# MCPS_Power_030520.net
KiCad netlist of a schematic drawn in Altium Designer
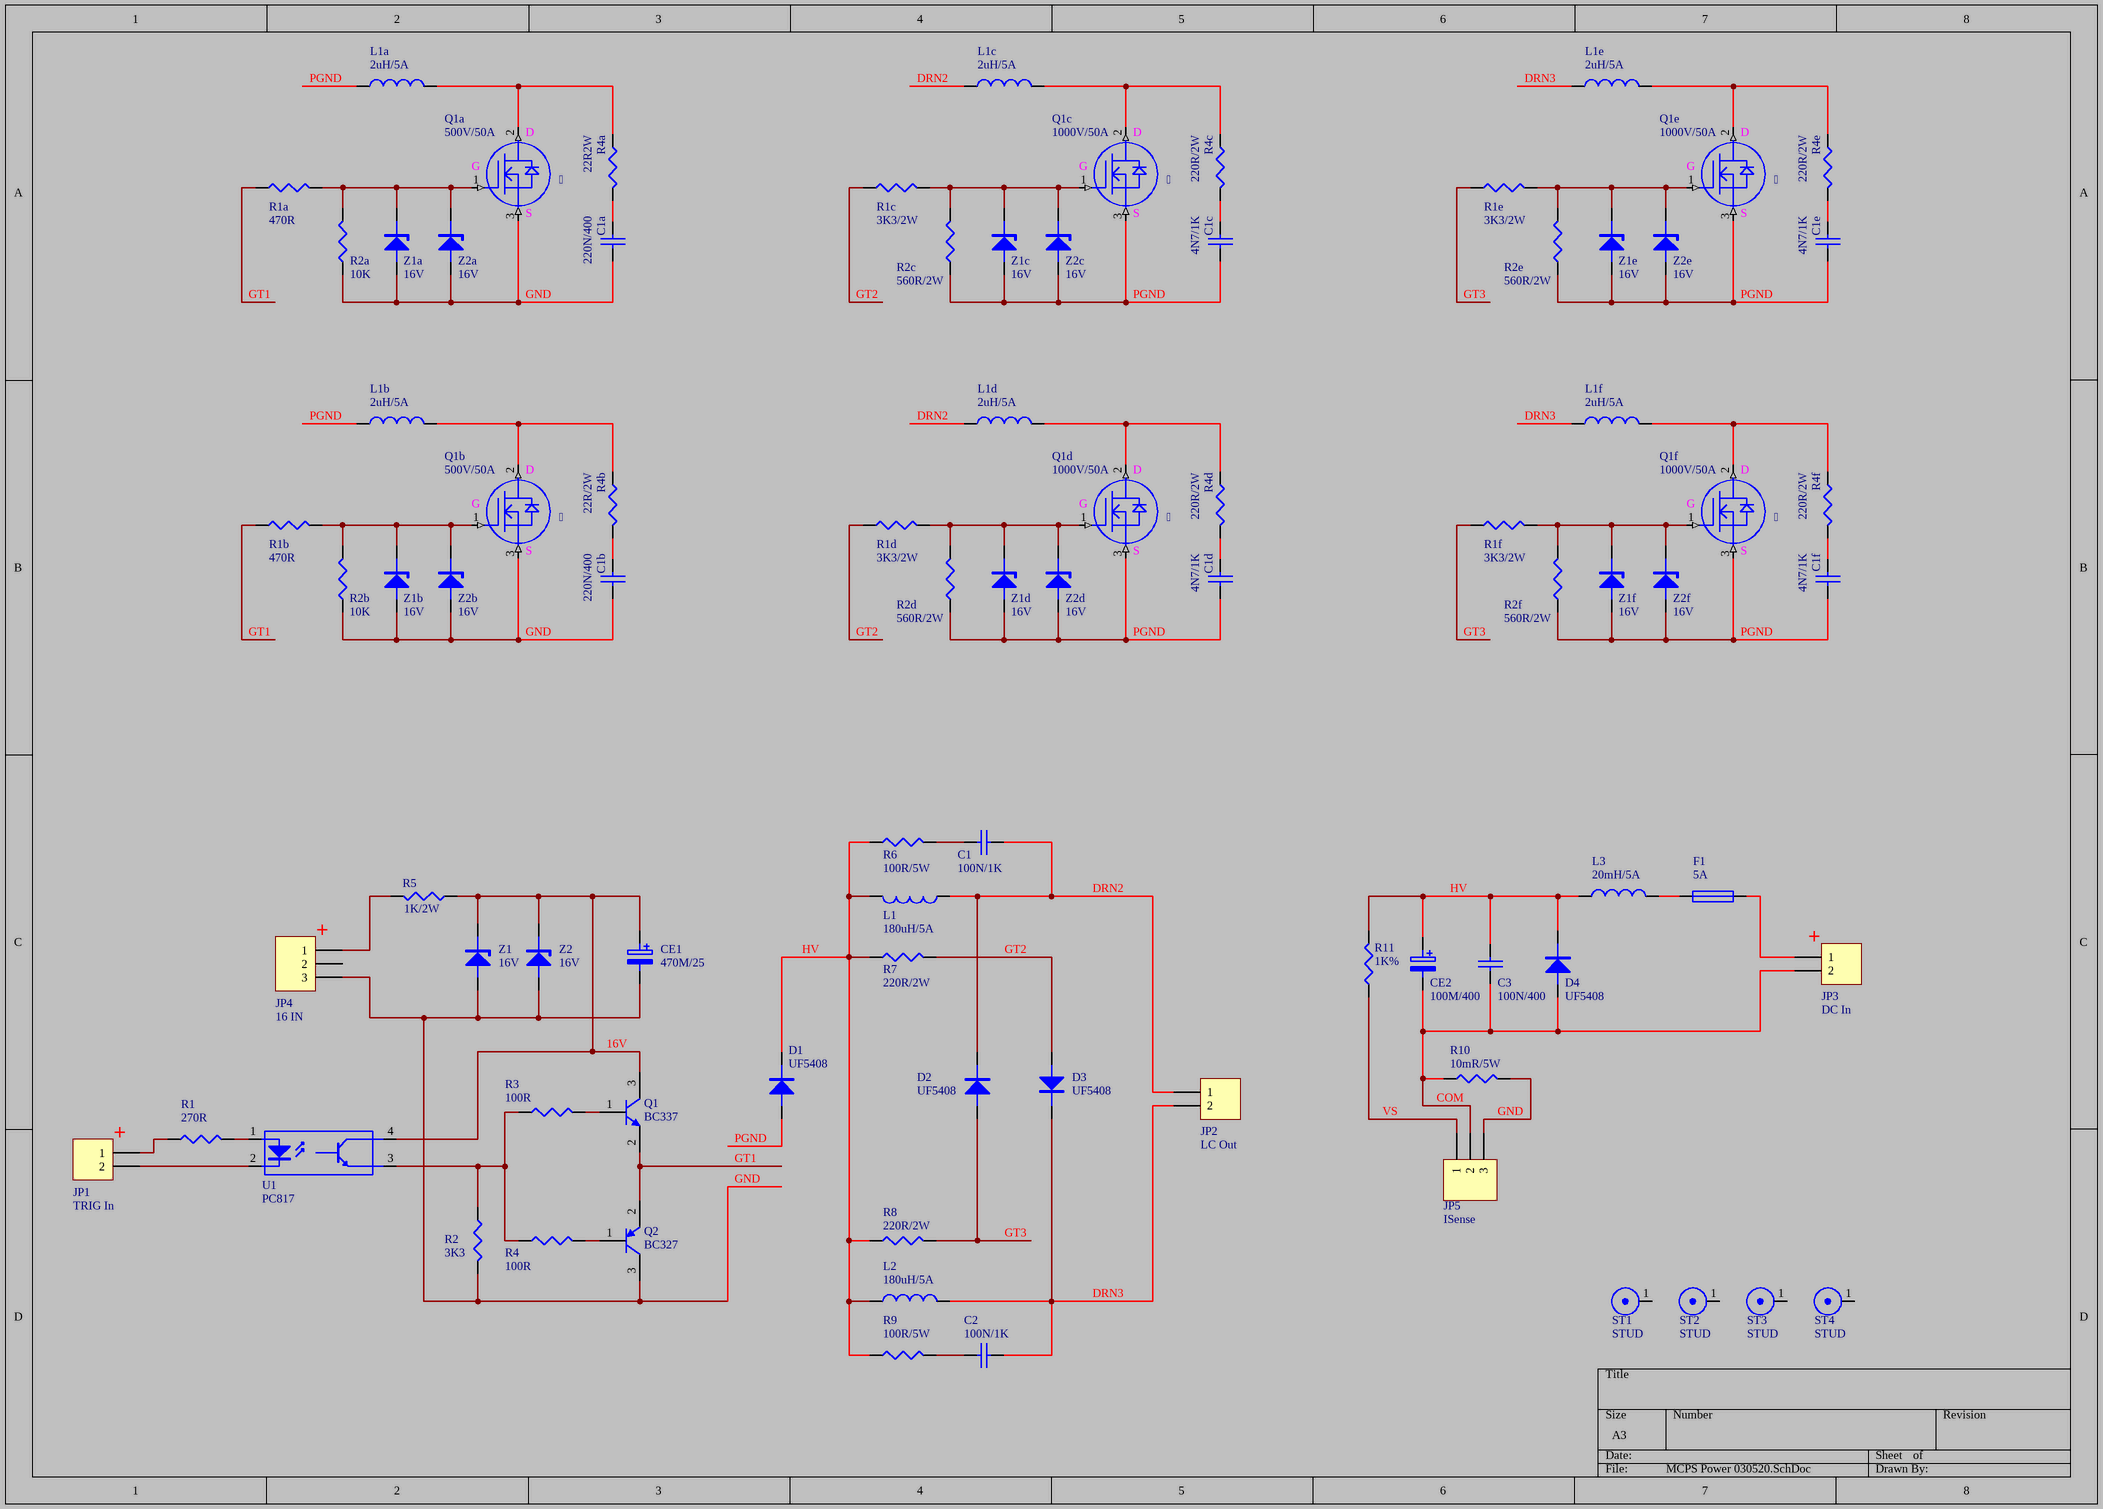
[diagram p0: MCPS Power 030520.SchDoc]

(export (version "E")
  (design (tool "Eeschema 10.0.6"))
  (components
    (comp (ref "C1") (value "100N/1K") (footprint "C100N") (libsource (lib "*") (part "C")))
    (comp (ref "C1a") (value "220N/400") (footprint "C4P") (libsource (lib "*") (part "C")))
    (comp (ref "C1b") (value "220N/400") (footprint "C4P") (libsource (lib "*") (part "C")))
    (comp (ref "C1c") (value "4N7/1K") (footprint "C4P") (libsource (lib "*") (part "C")))
    (comp (ref "C1d") (value "4N7/1K") (footprint "C4P") (libsource (lib "*") (part "C")))
    (comp (ref "C1e") (value "4N7/1K") (footprint "C4P") (libsource (lib "*") (part "C")))
    (comp (ref "C1f") (value "4N7/1K") (footprint "C4P") (libsource (lib "*") (part "C")))
    (comp (ref "C2") (value "100N/1K") (footprint "C100N") (libsource (lib "*") (part "C")))
    (comp (ref "C3") (value "100N/400") (footprint "C4P") (libsource (lib "*") (part "C")))
    (comp (ref "CE1") (value "470M/25") (footprint "cap2p12") (libsource (lib "*") (part "E")))
    (comp (ref "CE2") (value "100M/400") (footprint "CAP3P5") (libsource (lib "*") (part "E")))
    (comp (ref "D1") (value "UF5408") (footprint "D54") (libsource (lib "MyAltiumLib9702") (part "D")))
    (comp (ref "D2") (value "UF5408") (footprint "D54") (libsource (lib "MyAltiumLib9702") (part "D")))
    (comp (ref "D3") (value "UF5408") (footprint "D54") (libsource (lib "MyAltiumLib9702") (part "D")))
    (comp (ref "D4") (value "UF5408") (footprint "D54") (libsource (lib "MyAltiumLib9702") (part "D")))
    (comp (ref "F1") (value "5A") (footprint "FL") (libsource (lib "1402 Schlib 2020") (part "FUSE1")))
    (comp (ref "JP1")
      (value "TRIG In")
      (footprint "DSIP2")
      (description "Header, 2-Pin")
      (fields (field (name "PUBLISHER") "Altium Limited"))
      (libsource (lib "") (part "Header 2_1"))
    )
    (comp (ref "JP2")
      (value "LC Out")
      (footprint "DG55X2")
      (description "Header, 2-Pin")
      (fields (field (name "PUBLISHER") "Altium Limited"))
      (libsource (lib "Miscellaneous Connectors") (part "Header 2"))
    )
    (comp (ref "JP3")
      (value "DC In")
      (footprint "DG55X2")
      (description "Header, 2-Pin")
      (fields (field (name "PUBLISHER") "Altium Limited"))
      (libsource (lib "Miscellaneous Connectors") (part "Header 2"))
    )
    (comp (ref "JP4")
      (value "16 IN")
      (footprint "DSIP3")
      (description "Header, 3-Pin")
      (fields (field (name "PUBLISHER") "Altium Limited"))
      (libsource (lib "") (part "Header 3_1"))
    )
    (comp (ref "JP5")
      (value "ISense")
      (footprint "DSIP3")
      (description "Header, 3-Pin")
      (fields (field (name "PUBLISHER") "Altium Limited"))
      (libsource (lib "1403 Schlib 2020") (part "Header 3"))
    )
    (comp (ref "L1") (value "180uH/5A") (footprint "L20MHGREEN") (libsource (lib "") (part "INDUCTOR_1")))
    (comp (ref "L1a")
      (value "2uH/5A")
      (footprint "LS_GREEN")
      (libsource (lib "MyAltiumLib9702") (part "INDUCTOR"))
    )
    (comp (ref "L1b")
      (value "2uH/5A")
      (footprint "LS_GREEN")
      (libsource (lib "MyAltiumLib9702") (part "INDUCTOR"))
    )
    (comp (ref "L1c")
      (value "2uH/5A")
      (footprint "LS_GREEN")
      (libsource (lib "MyAltiumLib9702") (part "INDUCTOR"))
    )
    (comp (ref "L1d")
      (value "2uH/5A")
      (footprint "LS_GREEN")
      (libsource (lib "MyAltiumLib9702") (part "INDUCTOR"))
    )
    (comp (ref "L1e")
      (value "2uH/5A")
      (footprint "LS_GREEN")
      (libsource (lib "MyAltiumLib9702") (part "INDUCTOR"))
    )
    (comp (ref "L1f")
      (value "2uH/5A")
      (footprint "LS_GREEN")
      (libsource (lib "MyAltiumLib9702") (part "INDUCTOR"))
    )
    (comp (ref "L2")
      (value "180uH/5A")
      (footprint "L20MHGREEN")
      (libsource (lib "MyAltiumLib9702") (part "INDUCTOR"))
    )
    (comp (ref "L3")
      (value "20mH/5A")
      (footprint "L20MHGREEN")
      (libsource (lib "MyAltiumLib9702") (part "INDUCTOR"))
    )
    (comp (ref "Q1")
      (value "BC337")
      (footprint "CBE-BC546")
      (libsource (lib "1402 Schlib 2020") (part "BC546"))
    )
    (comp (ref "Q1a")
      (value "")
      (footprint "3EDG-STR")
      (libsource (lib "1402 Schlib 2020") (part "MOSFET N"))
    )
    (comp (ref "Q1b")
      (value "")
      (footprint "3EDG-STR")
      (libsource (lib "1402 Schlib 2020") (part "MOSFET N"))
    )
    (comp (ref "Q1c")
      (value "")
      (footprint "3EDG-STR")
      (libsource (lib "1402 Schlib 2020") (part "MOSFET N"))
    )
    (comp (ref "Q1d")
      (value "")
      (footprint "3EDG-STR")
      (libsource (lib "1402 Schlib 2020") (part "MOSFET N"))
    )
    (comp (ref "Q1e")
      (value "")
      (footprint "3EDG-STR")
      (libsource (lib "1402 Schlib 2020") (part "MOSFET N"))
    )
    (comp (ref "Q1f")
      (value "")
      (footprint "3EDG-STR")
      (libsource (lib "1402 Schlib 2020") (part "MOSFET N"))
    )
    (comp (ref "Q2")
      (value "BC327")
      (footprint "CBE-BC546")
      (description "PNP")
      (fields (field (name "PUBLISHER") "Altium Limited"))
      (libsource (lib "1402 Schlib 2020") (part "M6"))
    )
    (comp (ref "R1") (value "270R") (footprint "W1/4") (libsource (lib "*") (part "R")))
    (comp (ref "R1a") (value "470R") (footprint "R5P") (libsource (lib "*") (part "R")))
    (comp (ref "R1b") (value "470R") (footprint "R5P") (libsource (lib "*") (part "R")))
    (comp (ref "R1c") (value "3K3/2W") (footprint "R2W") (libsource (lib "*") (part "R")))
    (comp (ref "R1d") (value "3K3/2W") (footprint "R2W") (libsource (lib "*") (part "R")))
    (comp (ref "R1e") (value "3K3/2W") (footprint "R2W") (libsource (lib "*") (part "R")))
    (comp (ref "R1f") (value "3K3/2W") (footprint "R2W") (libsource (lib "*") (part "R")))
    (comp (ref "R2") (value "3K3") (footprint "W1/4") (libsource (lib "*") (part "R")))
    (comp (ref "R2a") (value "10K") (footprint "R5P") (libsource (lib "*") (part "R")))
    (comp (ref "R2b") (value "10K") (footprint "R5P") (libsource (lib "*") (part "R")))
    (comp (ref "R2c") (value "560R/2W") (footprint "R2W") (libsource (lib "*") (part "R")))
    (comp (ref "R2d") (value "560R/2W") (footprint "R2W") (libsource (lib "*") (part "R")))
    (comp (ref "R2e") (value "560R/2W") (footprint "R2W") (libsource (lib "*") (part "R")))
    (comp (ref "R2f") (value "560R/2W") (footprint "R2W") (libsource (lib "*") (part "R")))
    (comp (ref "R3") (value "100R") (footprint "W1/4") (libsource (lib "*") (part "R")))
    (comp (ref "R4") (value "100R") (footprint "W1/4") (libsource (lib "*") (part "R")))
    (comp (ref "R4a") (value "22R2W") (footprint "R2W") (libsource (lib "*") (part "R")))
    (comp (ref "R4b") (value "22R/2W") (footprint "R2W") (libsource (lib "*") (part "R")))
    (comp (ref "R4c") (value "220R/2W") (footprint "R2W") (libsource (lib "*") (part "R")))
    (comp (ref "R4d") (value "220R/2W") (footprint "R2W") (libsource (lib "*") (part "R")))
    (comp (ref "R4e") (value "220R/2W") (footprint "R2W") (libsource (lib "*") (part "R")))
    (comp (ref "R4f") (value "220R/2W") (footprint "R2W") (libsource (lib "*") (part "R")))
    (comp (ref "R5") (value "1K/2W") (footprint "R2W") (libsource (lib "*") (part "R")))
    (comp (ref "R6") (value "100R/5W") (footprint "R5W") (libsource (lib "*") (part "R")))
    (comp (ref "R7") (value "220R/2W") (footprint "R2W") (libsource (lib "*") (part "R")))
    (comp (ref "R8") (value "220R/2W") (footprint "R2W") (libsource (lib "*") (part "R")))
    (comp (ref "R9") (value "100R/5W") (footprint "R5W") (libsource (lib "*") (part "R")))
    (comp (ref "R10") (value "10mR/5W") (footprint "R5W") (libsource (lib "*") (part "R")))
    (comp (ref "R11") (value "1K%") (footprint "R5P") (libsource (lib "*") (part "R")))
    (comp (ref "ST1") (value "STUD") (footprint "CORNER") (libsource (lib "1402 Schlib 2020") (part "STUD")))
    (comp (ref "ST2") (value "STUD") (footprint "CORNER") (libsource (lib "1402 Schlib 2020") (part "STUD")))
    (comp (ref "ST3") (value "STUD") (footprint "CORNER") (libsource (lib "1402 Schlib 2020") (part "STUD")))
    (comp (ref "ST4") (value "STUD") (footprint "CORNER") (libsource (lib "1402 Schlib 2020") (part "STUD")))
    (comp (ref "U1")
      (value "PC817")
      (footprint "DIP4")
      (libsource (lib "1402 Schlib 2020") (part "OPTODIP4"))
    )
    (comp (ref "Z1") (value "16V") (footprint "D5P") (libsource (lib "MyAltiumLib9702") (part "DZ")))
    (comp (ref "Z1a") (value "16V") (footprint "D5P") (libsource (lib "MyAltiumLib9702") (part "DZ")))
    (comp (ref "Z1b") (value "16V") (footprint "D5P") (libsource (lib "MyAltiumLib9702") (part "DZ")))
    (comp (ref "Z1c") (value "16V") (footprint "D5P") (libsource (lib "MyAltiumLib9702") (part "DZ")))
    (comp (ref "Z1d") (value "16V") (footprint "D5P") (libsource (lib "MyAltiumLib9702") (part "DZ")))
    (comp (ref "Z1e") (value "16V") (footprint "D5P") (libsource (lib "MyAltiumLib9702") (part "DZ")))
    (comp (ref "Z1f") (value "16V") (footprint "D5P") (libsource (lib "MyAltiumLib9702") (part "DZ")))
    (comp (ref "Z2") (value "16V") (footprint "D5P") (libsource (lib "MyAltiumLib9702") (part "DZ")))
    (comp (ref "Z2a") (value "16V") (footprint "D5P") (libsource (lib "MyAltiumLib9702") (part "DZ")))
    (comp (ref "Z2b") (value "16V") (footprint "D5P") (libsource (lib "MyAltiumLib9702") (part "DZ")))
    (comp (ref "Z2c") (value "16V") (footprint "D5P") (libsource (lib "MyAltiumLib9702") (part "DZ")))
    (comp (ref "Z2d") (value "16V") (footprint "D5P") (libsource (lib "MyAltiumLib9702") (part "DZ")))
    (comp (ref "Z2e") (value "16V") (footprint "D5P") (libsource (lib "MyAltiumLib9702") (part "DZ")))
    (comp (ref "Z2f") (value "16V") (footprint "D5P") (libsource (lib "MyAltiumLib9702") (part "DZ")))
  )
  (nets
    (net (code "1") (name "/16V") (class "Default")
      (node (ref "CE1") (pin "1") (pintype "passive"))
      (node (ref "Q1") (pin "3") (pinfunction "C_3") (pintype "passive"))
      (node (ref "R5") (pin "1") (pintype "passive"))
      (node (ref "U1") (pin "4") (pinfunction "C_4") (pintype "passive"))
      (node (ref "Z1") (pin "2") (pinfunction "K_2") (pintype "passive"))
      (node (ref "Z2") (pin "2") (pinfunction "K_2") (pintype "passive"))
    )
    (net (code "2") (name "/COM") (class "Default")
      (node (ref "C3") (pin "2") (pintype "passive"))
      (node (ref "CE2") (pin "2") (pintype "passive"))
      (node (ref "D4") (pin "1") (pinfunction "A_1") (pintype "passive"))
      (node (ref "JP3") (pin "2") (pinfunction "2_2") (pintype "passive"))
      (node (ref "JP5") (pin "2") (pinfunction "2_2") (pintype "passive"))
      (node (ref "R10") (pin "1") (pintype "passive"))
    )
    (net (code "3") (name "/DRN2") (class "Default")
      (node (ref "C1") (pin "2") (pintype "passive"))
      (node (ref "D2") (pin "2") (pinfunction "K_2") (pintype "passive"))
      (node (ref "JP2") (pin "1") (pinfunction "1_1") (pintype "passive"))
      (node (ref "L1") (pin "2") (pinfunction "2_2") (pintype "passive"))
      (node (ref "L1c") (pin "1") (pinfunction "1_1") (pintype "passive"))
      (node (ref "L1d") (pin "1") (pinfunction "1_1") (pintype "passive"))
    )
    (net (code "4") (name "/DRN3") (class "Default")
      (node (ref "C2") (pin "2") (pintype "passive"))
      (node (ref "D3") (pin "2") (pinfunction "K_2") (pintype "passive"))
      (node (ref "JP2") (pin "2") (pinfunction "2_2") (pintype "passive"))
      (node (ref "L1e") (pin "1") (pinfunction "1_1") (pintype "passive"))
      (node (ref "L1f") (pin "1") (pinfunction "1_1") (pintype "passive"))
      (node (ref "L2") (pin "2") (pinfunction "2_2") (pintype "passive"))
    )
    (net (code "5") (name "/GND") (class "Default")
      (node (ref "C1a") (pin "2") (pintype "passive"))
      (node (ref "C1b") (pin "2") (pintype "passive"))
      (node (ref "CE1") (pin "2") (pintype "passive"))
      (node (ref "JP4") (pin "3") (pinfunction "3_3") (pintype "passive"))
      (node (ref "JP5") (pin "3") (pinfunction "3_3") (pintype "passive"))
      (node (ref "Q1a") (pin "3") (pinfunction "S_3") (pintype "input"))
      (node (ref "Q1b") (pin "3") (pinfunction "S_3") (pintype "input"))
      (node (ref "Q2") (pin "3") (pinfunction "C_3") (pintype "passive"))
      (node (ref "R10") (pin "2") (pintype "passive"))
      (node (ref "R2") (pin "2") (pintype "passive"))
      (node (ref "R2a") (pin "1") (pintype "passive"))
      (node (ref "R2b") (pin "1") (pintype "passive"))
      (node (ref "Z1") (pin "1") (pinfunction "A_1") (pintype "passive"))
      (node (ref "Z1a") (pin "1") (pinfunction "A_1") (pintype "passive"))
      (node (ref "Z1b") (pin "1") (pinfunction "A_1") (pintype "passive"))
      (node (ref "Z2") (pin "1") (pinfunction "A_1") (pintype "passive"))
      (node (ref "Z2a") (pin "1") (pinfunction "A_1") (pintype "passive"))
      (node (ref "Z2b") (pin "1") (pinfunction "A_1") (pintype "passive"))
    )
    (net (code "6") (name "/GT1") (class "Default")
      (node (ref "Q1") (pin "2") (pinfunction "E_2") (pintype "passive"))
      (node (ref "Q2") (pin "2") (pinfunction "B_2") (pintype "passive"))
      (node (ref "R1a") (pin "1") (pintype "passive"))
      (node (ref "R1b") (pin "1") (pintype "passive"))
    )
    (net (code "7") (name "/GT2") (class "Default")
      (node (ref "D3") (pin "1") (pinfunction "A_1") (pintype "passive"))
      (node (ref "R1c") (pin "1") (pintype "passive"))
      (node (ref "R1d") (pin "1") (pintype "passive"))
      (node (ref "R7") (pin "2") (pintype "passive"))
    )
    (net (code "8") (name "/GT3") (class "Default")
      (node (ref "D2") (pin "1") (pinfunction "A_1") (pintype "passive"))
      (node (ref "R1e") (pin "1") (pintype "passive"))
      (node (ref "R1f") (pin "1") (pintype "passive"))
      (node (ref "R8") (pin "2") (pintype "passive"))
    )
    (net (code "9") (name "/HV") (class "Default")
      (node (ref "C3") (pin "1") (pintype "passive"))
      (node (ref "CE2") (pin "1") (pintype "passive"))
      (node (ref "D1") (pin "2") (pinfunction "K_2") (pintype "passive"))
      (node (ref "D4") (pin "2") (pinfunction "K_2") (pintype "passive"))
      (node (ref "L1") (pin "1") (pinfunction "1_1") (pintype "passive"))
      (node (ref "L2") (pin "1") (pinfunction "1_1") (pintype "passive"))
      (node (ref "L3") (pin "1") (pinfunction "1_1") (pintype "passive"))
      (node (ref "R11") (pin "2") (pintype "passive"))
      (node (ref "R6") (pin "1") (pintype "passive"))
      (node (ref "R7") (pin "1") (pintype "passive"))
      (node (ref "R8") (pin "1") (pintype "passive"))
      (node (ref "R9") (pin "1") (pintype "passive"))
    )
    (net (code "10") (name "/PGND") (class "Default")
      (node (ref "C1c") (pin "2") (pintype "passive"))
      (node (ref "C1d") (pin "2") (pintype "passive"))
      (node (ref "C1e") (pin "2") (pintype "passive"))
      (node (ref "C1f") (pin "2") (pintype "passive"))
      (node (ref "D1") (pin "1") (pinfunction "A_1") (pintype "passive"))
      (node (ref "L1a") (pin "1") (pinfunction "1_1") (pintype "passive"))
      (node (ref "L1b") (pin "1") (pinfunction "1_1") (pintype "passive"))
      (node (ref "Q1c") (pin "3") (pinfunction "S_3") (pintype "input"))
      (node (ref "Q1d") (pin "3") (pinfunction "S_3") (pintype "input"))
      (node (ref "Q1e") (pin "3") (pinfunction "S_3") (pintype "input"))
      (node (ref "Q1f") (pin "3") (pinfunction "S_3") (pintype "input"))
      (node (ref "R2c") (pin "1") (pintype "passive"))
      (node (ref "R2d") (pin "1") (pintype "passive"))
      (node (ref "R2e") (pin "1") (pintype "passive"))
      (node (ref "R2f") (pin "1") (pintype "passive"))
      (node (ref "Z1c") (pin "1") (pinfunction "A_1") (pintype "passive"))
      (node (ref "Z1d") (pin "1") (pinfunction "A_1") (pintype "passive"))
      (node (ref "Z1e") (pin "1") (pinfunction "A_1") (pintype "passive"))
      (node (ref "Z1f") (pin "1") (pinfunction "A_1") (pintype "passive"))
      (node (ref "Z2c") (pin "1") (pinfunction "A_1") (pintype "passive"))
      (node (ref "Z2d") (pin "1") (pinfunction "A_1") (pintype "passive"))
      (node (ref "Z2e") (pin "1") (pinfunction "A_1") (pintype "passive"))
      (node (ref "Z2f") (pin "1") (pinfunction "A_1") (pintype "passive"))
    )
    (net (code "11") (name "/VS") (class "Default")
      (node (ref "JP5") (pin "1") (pinfunction "1_1") (pintype "passive"))
      (node (ref "R11") (pin "1") (pintype "passive"))
    )
    (net (code "12") (name "Net-(C1-Pad1)") (class "Default")
      (node (ref "C1") (pin "1") (pintype "passive"))
      (node (ref "R6") (pin "2") (pintype "passive"))
    )
    (net (code "13") (name "Net-(C1a-Pad1)") (class "Default")
      (node (ref "C1a") (pin "1") (pintype "passive"))
      (node (ref "R4a") (pin "2") (pintype "passive"))
    )
    (net (code "14") (name "Net-(C1b-Pad1)") (class "Default")
      (node (ref "C1b") (pin "1") (pintype "passive"))
      (node (ref "R4b") (pin "2") (pintype "passive"))
    )
    (net (code "15") (name "Net-(C1c-Pad1)") (class "Default")
      (node (ref "C1c") (pin "1") (pintype "passive"))
      (node (ref "R4c") (pin "2") (pintype "passive"))
    )
    (net (code "16") (name "Net-(C1d-Pad1)") (class "Default")
      (node (ref "C1d") (pin "1") (pintype "passive"))
      (node (ref "R4d") (pin "2") (pintype "passive"))
    )
    (net (code "17") (name "Net-(C1e-Pad1)") (class "Default")
      (node (ref "C1e") (pin "1") (pintype "passive"))
      (node (ref "R4e") (pin "2") (pintype "passive"))
    )
    (net (code "18") (name "Net-(C1f-Pad1)") (class "Default")
      (node (ref "C1f") (pin "1") (pintype "passive"))
      (node (ref "R4f") (pin "2") (pintype "passive"))
    )
    (net (code "19") (name "Net-(C2-Pad1)") (class "Default")
      (node (ref "C2") (pin "1") (pintype "passive"))
      (node (ref "R9") (pin "2") (pintype "passive"))
    )
    (net (code "20") (name "Net-(F1-Pad1)") (class "Default")
      (node (ref "F1") (pin "1") (pintype "passive"))
      (node (ref "L3") (pin "2") (pinfunction "2_2") (pintype "passive"))
    )
    (net (code "21") (name "Net-(F1-Pad2)") (class "Default")
      (node (ref "F1") (pin "2") (pintype "passive"))
      (node (ref "JP3") (pin "1") (pinfunction "1_1") (pintype "passive"))
    )
    (net (code "22") (name "Net-(JP1-Pad1)") (class "Default")
      (node (ref "JP1") (pin "1") (pinfunction "1_1") (pintype "passive"))
      (node (ref "R1") (pin "1") (pintype "passive"))
    )
    (net (code "23") (name "Net-(JP4-Pad1)") (class "Default")
      (node (ref "JP4") (pin "1") (pinfunction "1_1") (pintype "passive"))
      (node (ref "R5") (pin "2") (pintype "passive"))
    )
    (net (code "24") (name "Net-(Q1-B)") (class "Default")
      (node (ref "Q1") (pin "1") (pinfunction "B_1") (pintype "passive"))
      (node (ref "R3") (pin "2") (pintype "passive"))
    )
    (net (code "25") (name "Net-(Q1a-D)") (class "Default")
      (node (ref "L1a") (pin "2") (pinfunction "2_2") (pintype "passive"))
      (node (ref "Q1a") (pin "2") (pinfunction "D_2") (pintype "output"))
      (node (ref "R4a") (pin "1") (pintype "passive"))
    )
    (net (code "26") (name "Net-(Q1a-G)") (class "Default")
      (node (ref "Q1a") (pin "1") (pinfunction "G_1") (pintype "input"))
      (node (ref "R1a") (pin "2") (pintype "passive"))
      (node (ref "R2a") (pin "2") (pintype "passive"))
      (node (ref "Z1a") (pin "2") (pinfunction "K_2") (pintype "passive"))
      (node (ref "Z2a") (pin "2") (pinfunction "K_2") (pintype "passive"))
    )
    (net (code "27") (name "Net-(Q1b-D)") (class "Default")
      (node (ref "L1b") (pin "2") (pinfunction "2_2") (pintype "passive"))
      (node (ref "Q1b") (pin "2") (pinfunction "D_2") (pintype "output"))
      (node (ref "R4b") (pin "1") (pintype "passive"))
    )
    (net (code "28") (name "Net-(Q1b-G)") (class "Default")
      (node (ref "Q1b") (pin "1") (pinfunction "G_1") (pintype "input"))
      (node (ref "R1b") (pin "2") (pintype "passive"))
      (node (ref "R2b") (pin "2") (pintype "passive"))
      (node (ref "Z1b") (pin "2") (pinfunction "K_2") (pintype "passive"))
      (node (ref "Z2b") (pin "2") (pinfunction "K_2") (pintype "passive"))
    )
    (net (code "29") (name "Net-(Q1c-D)") (class "Default")
      (node (ref "L1c") (pin "2") (pinfunction "2_2") (pintype "passive"))
      (node (ref "Q1c") (pin "2") (pinfunction "D_2") (pintype "output"))
      (node (ref "R4c") (pin "1") (pintype "passive"))
    )
    (net (code "30") (name "Net-(Q1c-G)") (class "Default")
      (node (ref "Q1c") (pin "1") (pinfunction "G_1") (pintype "input"))
      (node (ref "R1c") (pin "2") (pintype "passive"))
      (node (ref "R2c") (pin "2") (pintype "passive"))
      (node (ref "Z1c") (pin "2") (pinfunction "K_2") (pintype "passive"))
      (node (ref "Z2c") (pin "2") (pinfunction "K_2") (pintype "passive"))
    )
    (net (code "31") (name "Net-(Q1d-D)") (class "Default")
      (node (ref "L1d") (pin "2") (pinfunction "2_2") (pintype "passive"))
      (node (ref "Q1d") (pin "2") (pinfunction "D_2") (pintype "output"))
      (node (ref "R4d") (pin "1") (pintype "passive"))
    )
    (net (code "32") (name "Net-(Q1d-G)") (class "Default")
      (node (ref "Q1d") (pin "1") (pinfunction "G_1") (pintype "input"))
      (node (ref "R1d") (pin "2") (pintype "passive"))
      (node (ref "R2d") (pin "2") (pintype "passive"))
      (node (ref "Z1d") (pin "2") (pinfunction "K_2") (pintype "passive"))
      (node (ref "Z2d") (pin "2") (pinfunction "K_2") (pintype "passive"))
    )
    (net (code "33") (name "Net-(Q1e-D)") (class "Default")
      (node (ref "L1e") (pin "2") (pinfunction "2_2") (pintype "passive"))
      (node (ref "Q1e") (pin "2") (pinfunction "D_2") (pintype "output"))
      (node (ref "R4e") (pin "1") (pintype "passive"))
    )
    (net (code "34") (name "Net-(Q1e-G)") (class "Default")
      (node (ref "Q1e") (pin "1") (pinfunction "G_1") (pintype "input"))
      (node (ref "R1e") (pin "2") (pintype "passive"))
      (node (ref "R2e") (pin "2") (pintype "passive"))
      (node (ref "Z1e") (pin "2") (pinfunction "K_2") (pintype "passive"))
      (node (ref "Z2e") (pin "2") (pinfunction "K_2") (pintype "passive"))
    )
    (net (code "35") (name "Net-(Q1f-D)") (class "Default")
      (node (ref "L1f") (pin "2") (pinfunction "2_2") (pintype "passive"))
      (node (ref "Q1f") (pin "2") (pinfunction "D_2") (pintype "output"))
      (node (ref "R4f") (pin "1") (pintype "passive"))
    )
    (net (code "36") (name "Net-(Q1f-G)") (class "Default")
      (node (ref "Q1f") (pin "1") (pinfunction "G_1") (pintype "input"))
      (node (ref "R1f") (pin "2") (pintype "passive"))
      (node (ref "R2f") (pin "2") (pintype "passive"))
      (node (ref "Z1f") (pin "2") (pinfunction "K_2") (pintype "passive"))
      (node (ref "Z2f") (pin "2") (pinfunction "K_2") (pintype "passive"))
    )
    (net (code "37") (name "Net-(Q2-E)") (class "Default")
      (node (ref "Q2") (pin "1") (pinfunction "E_1") (pintype "passive"))
      (node (ref "R4") (pin "2") (pintype "passive"))
    )
    (net (code "38") (name "Net-(U1-A)") (class "Default")
      (node (ref "R1") (pin "2") (pintype "passive"))
      (node (ref "U1") (pin "1") (pinfunction "A_1") (pintype "passive"))
    )
    (net (code "39") (name "Net-(U1-E)") (class "Default")
      (node (ref "R2") (pin "1") (pintype "passive"))
      (node (ref "R3") (pin "1") (pintype "passive"))
      (node (ref "R4") (pin "1") (pintype "passive"))
      (node (ref "U1") (pin "3") (pinfunction "E_3") (pintype "passive"))
    )
    (net (code "40") (name "Net-(U1-K)") (class "Default")
      (node (ref "JP1") (pin "2") (pinfunction "2_2") (pintype "passive"))
      (node (ref "U1") (pin "2") (pinfunction "K_2") (pintype "passive"))
    )
    (net (code "41") (name "unconnected-(JP4-Pad2)") (class "Default")
      (node (ref "JP4") (pin "2") (pinfunction "2_2") (pintype "passive"))
    )
    (net (code "42") (name "unconnected-(ST1-Pad1)") (class "Default")
      (node (ref "ST1") (pin "1") (pintype "passive"))
    )
    (net (code "43") (name "unconnected-(ST2-Pad1)") (class "Default")
      (node (ref "ST2") (pin "1") (pintype "passive"))
    )
    (net (code "44") (name "unconnected-(ST3-Pad1)") (class "Default")
      (node (ref "ST3") (pin "1") (pintype "passive"))
    )
    (net (code "45") (name "unconnected-(ST4-Pad1)") (class "Default")
      (node (ref "ST4") (pin "1") (pintype "passive"))
    )
  )
)
